# Sending_end.net
KiCad netlist of a schematic drawn in EAGLE
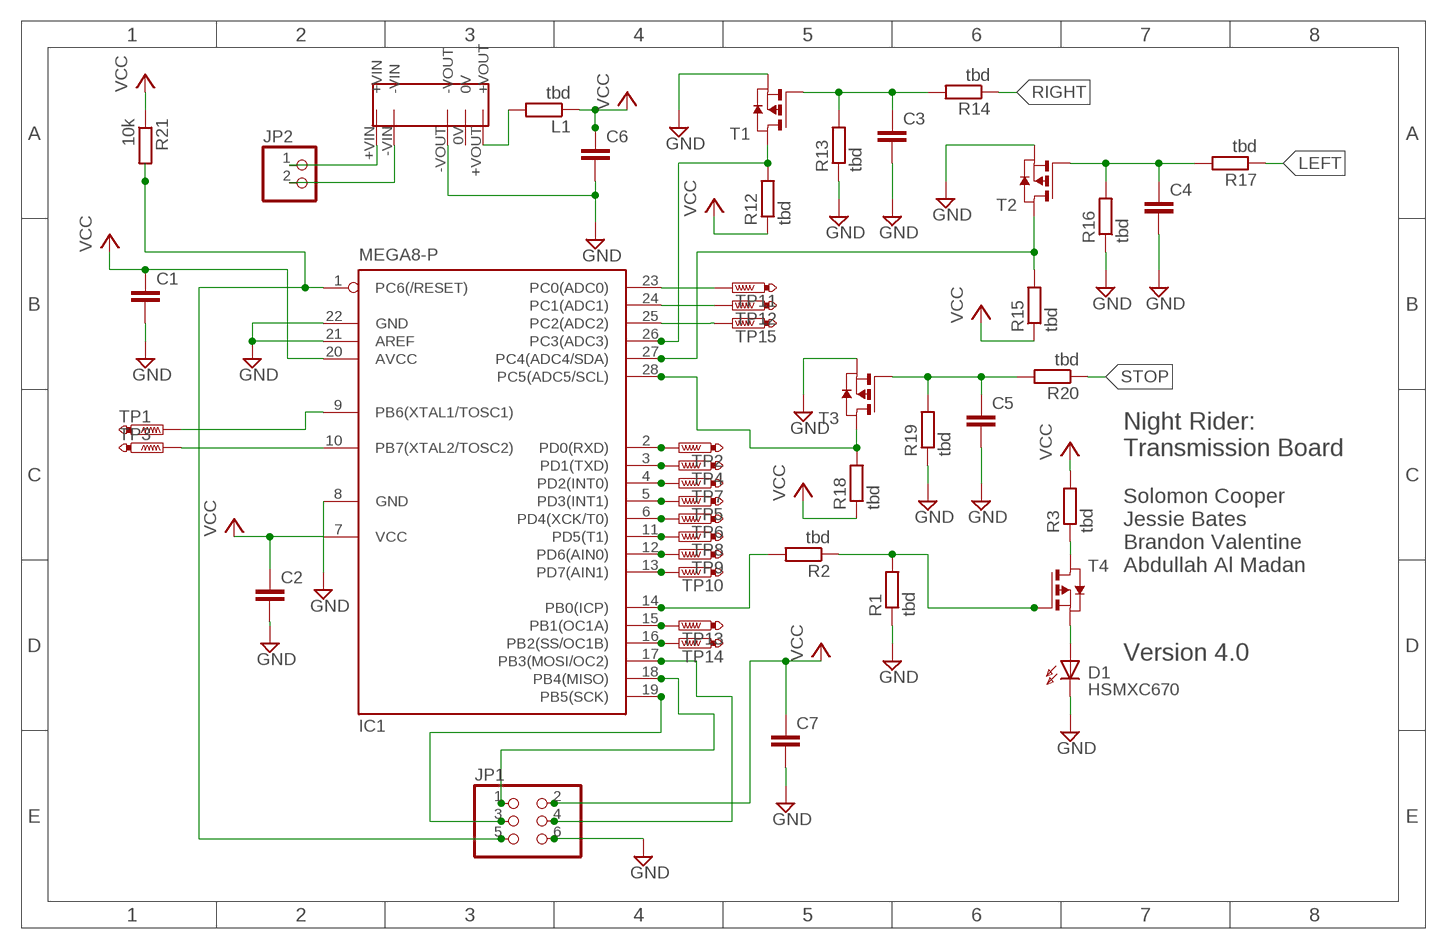
[diagram p0: schematic, sheet 1]

(export (version "E")
  (design (tool "Eeschema 10.0.6"))
  (components
    (comp (ref "C1")
      (value "C-EUC0805")
      (footprint "eagle-import:C0805")
      (libsource (lib "eagle-import") (part "C-EUC0805"))
    )
    (comp (ref "C2")
      (value "C-EUC0805")
      (footprint "eagle-import:C0805")
      (libsource (lib "eagle-import") (part "C-EUC0805"))
    )
    (comp (ref "C3")
      (value "C-EUC0805")
      (footprint "eagle-import:C0805")
      (libsource (lib "eagle-import") (part "C-EUC0805"))
    )
    (comp (ref "C4")
      (value "C-EUC0805")
      (footprint "eagle-import:C0805")
      (libsource (lib "eagle-import") (part "C-EUC0805"))
    )
    (comp (ref "C5")
      (value "C-EUC0805")
      (footprint "eagle-import:C0805")
      (libsource (lib "eagle-import") (part "C-EUC0805"))
    )
    (comp (ref "C6")
      (value "C-EUC0805")
      (footprint "eagle-import:C0805")
      (libsource (lib "eagle-import") (part "C-EUC0805"))
    )
    (comp (ref "C7")
      (value "C-EUC0805")
      (footprint "eagle-import:C0805")
      (libsource (lib "eagle-import") (part "C-EUC0805"))
    )
    (comp (ref "D1")
      (value "HSMXC670")
      (footprint "eagle-import:HSMXC670")
      (fields (field (name "OC_FARNELL") "unknown") (field (name "OC_NEWARK") "unknown"))
      (libsource (lib "eagle-import") (part "HSMXC670"))
    )
    (comp (ref "IC1")
      (value "MEGA8-P")
      (footprint "eagle-import:DIL28-3")
      (libsource (lib "eagle-import") (part "MEGA8-P"))
    )
    (comp (ref "JP1")
      (value "PINHD-2X3")
      (footprint "eagle-import:2X03")
      (libsource (lib "eagle-import") (part "PINHD-2X3"))
    )
    (comp (ref "JP2")
      (value "PINHD-1X2")
      (footprint "eagle-import:1X02")
      (libsource (lib "eagle-import") (part "PINHD-1X2"))
    )
    (comp (ref "L1")
      (value "tbd")
      (footprint "eagle-import:M0805")
      (libsource (lib "eagle-import") (part "R-EU_M0805"))
    )
    (comp (ref "R1")
      (value "tbd")
      (footprint "eagle-import:M0805")
      (libsource (lib "eagle-import") (part "R-EU_M0805"))
    )
    (comp (ref "R2")
      (value "tbd")
      (footprint "eagle-import:M0805")
      (libsource (lib "eagle-import") (part "R-EU_M0805"))
    )
    (comp (ref "R3")
      (value "tbd")
      (footprint "eagle-import:M0805")
      (libsource (lib "eagle-import") (part "R-EU_M0805"))
    )
    (comp (ref "R12")
      (value "tbd")
      (footprint "eagle-import:M0805")
      (libsource (lib "eagle-import") (part "R-EU_M0805"))
    )
    (comp (ref "R13")
      (value "tbd")
      (footprint "eagle-import:M0805")
      (libsource (lib "eagle-import") (part "R-EU_M0805"))
    )
    (comp (ref "R14")
      (value "tbd")
      (footprint "eagle-import:M0805")
      (libsource (lib "eagle-import") (part "R-EU_M0805"))
    )
    (comp (ref "R15")
      (value "tbd")
      (footprint "eagle-import:M0805")
      (libsource (lib "eagle-import") (part "R-EU_M0805"))
    )
    (comp (ref "R16")
      (value "tbd")
      (footprint "eagle-import:M0805")
      (libsource (lib "eagle-import") (part "R-EU_M0805"))
    )
    (comp (ref "R17")
      (value "tbd")
      (footprint "eagle-import:M0805")
      (libsource (lib "eagle-import") (part "R-EU_M0805"))
    )
    (comp (ref "R18")
      (value "tbd")
      (footprint "eagle-import:M0805")
      (libsource (lib "eagle-import") (part "R-EU_M0805"))
    )
    (comp (ref "R19")
      (value "tbd")
      (footprint "eagle-import:M0805")
      (libsource (lib "eagle-import") (part "R-EU_M0805"))
    )
    (comp (ref "R20")
      (value "tbd")
      (footprint "eagle-import:M0805")
      (libsource (lib "eagle-import") (part "R-EU_M0805"))
    )
    (comp (ref "R21")
      (value "10k")
      (footprint "eagle-import:M0805")
      (libsource (lib "eagle-import") (part "R-EU_M0805"))
    )
    (comp (ref "T1")
      (value "PMOSSOT23")
      (footprint "eagle-import:SOT-23")
      (libsource (lib "eagle-import") (part "PMOSSOT23"))
    )
    (comp (ref "T2")
      (value "PMOSSOT23")
      (footprint "eagle-import:SOT-23")
      (libsource (lib "eagle-import") (part "PMOSSOT23"))
    )
    (comp (ref "T3")
      (value "PMOSSOT23")
      (footprint "eagle-import:SOT-23")
      (libsource (lib "eagle-import") (part "PMOSSOT23"))
    )
    (comp (ref "T4")
      (value "PMOSSOT23")
      (footprint "eagle-import:SOT-23")
      (fields (field (name "OC_FARNELL") "unknown") (field (name "OC_NEWARK") "unknown"))
      (libsource (lib "eagle-import") (part "PMOSSOT23"))
    )
    (comp (ref "TP1")
      (value "PTR1PAD1-20")
      (footprint "eagle-import:P1-20")
      (libsource (lib "eagle-import") (part "PTR1PAD1-20"))
    )
    (comp (ref "TP2")
      (value "PTR1PAD1-20")
      (footprint "eagle-import:P1-20")
      (libsource (lib "eagle-import") (part "PTR1PAD1-20"))
    )
    (comp (ref "TP3")
      (value "PTR1PAD1-20")
      (footprint "eagle-import:P1-20")
      (libsource (lib "eagle-import") (part "PTR1PAD1-20"))
    )
    (comp (ref "TP4")
      (value "PTR1PAD1-20")
      (footprint "eagle-import:P1-20")
      (libsource (lib "eagle-import") (part "PTR1PAD1-20"))
    )
    (comp (ref "TP5")
      (value "PTR1PAD1-20")
      (footprint "eagle-import:P1-20")
      (libsource (lib "eagle-import") (part "PTR1PAD1-20"))
    )
    (comp (ref "TP6")
      (value "PTR1PAD1-20")
      (footprint "eagle-import:P1-20")
      (libsource (lib "eagle-import") (part "PTR1PAD1-20"))
    )
    (comp (ref "TP7")
      (value "PTR1PAD1-20")
      (footprint "eagle-import:P1-20")
      (libsource (lib "eagle-import") (part "PTR1PAD1-20"))
    )
    (comp (ref "TP8")
      (value "PTR1PAD1-20")
      (footprint "eagle-import:P1-20")
      (libsource (lib "eagle-import") (part "PTR1PAD1-20"))
    )
    (comp (ref "TP9")
      (value "PTR1PAD1-20")
      (footprint "eagle-import:P1-20")
      (libsource (lib "eagle-import") (part "PTR1PAD1-20"))
    )
    (comp (ref "TP10")
      (value "PTR1PAD1-20")
      (footprint "eagle-import:P1-20")
      (libsource (lib "eagle-import") (part "PTR1PAD1-20"))
    )
    (comp (ref "TP11")
      (value "PTR1PAD1-20")
      (footprint "eagle-import:P1-20")
      (libsource (lib "eagle-import") (part "PTR1PAD1-20"))
    )
    (comp (ref "TP12")
      (value "PTR1PAD1-20")
      (footprint "eagle-import:P1-20")
      (libsource (lib "eagle-import") (part "PTR1PAD1-20"))
    )
    (comp (ref "TP13")
      (value "PTR1PAD1-20")
      (footprint "eagle-import:P1-20")
      (libsource (lib "eagle-import") (part "PTR1PAD1-20"))
    )
    (comp (ref "TP14")
      (value "PTR1PAD1-20")
      (footprint "eagle-import:P1-20")
      (libsource (lib "eagle-import") (part "PTR1PAD1-20"))
    )
    (comp (ref "TP15")
      (value "PTR1PAD1-20")
      (footprint "eagle-import:P1-20")
      (libsource (lib "eagle-import") (part "PTR1PAD1-20"))
    )
    (comp (ref "U$1")
      (value "NKA1205SC")
      (footprint "eagle-import:NKA1205SC")
      (libsource (lib "eagle-import") (part "NKA1205SC"))
    )
  )
  (nets
    (net (code "1") (name "GND") (class "Default")
      (node (ref "C1") (pin "2") (pinfunction "2_2") (pintype "passive"))
      (node (ref "C2") (pin "2") (pinfunction "2_2") (pintype "passive"))
      (node (ref "C3") (pin "2") (pinfunction "2_2") (pintype "passive"))
      (node (ref "C4") (pin "2") (pinfunction "2_2") (pintype "passive"))
      (node (ref "C5") (pin "2") (pinfunction "2_2") (pintype "passive"))
      (node (ref "C6") (pin "2") (pinfunction "2_2") (pintype "passive"))
      (node (ref "C7") (pin "2") (pinfunction "2_2") (pintype "passive"))
      (node (ref "D1") (pin "K") (pinfunction "C_K") (pintype "passive"))
      (node (ref "IC1") (pin "21") (pinfunction "AREF_21") (pintype "passive"))
      (node (ref "IC1") (pin "22") (pinfunction "GND_22") (pintype "power_in"))
      (node (ref "IC1") (pin "8") (pinfunction "GND_8") (pintype "power_in"))
      (node (ref "JP1") (pin "6") (pinfunction "6_6") (pintype "passive"))
      (node (ref "R1") (pin "1") (pinfunction "1_1") (pintype "passive"))
      (node (ref "R13") (pin "1") (pinfunction "1_1") (pintype "passive"))
      (node (ref "R16") (pin "1") (pinfunction "1_1") (pintype "passive"))
      (node (ref "R19") (pin "1") (pinfunction "1_1") (pintype "passive"))
      (node (ref "T1") (pin "2") (pinfunction "S_2") (pintype "passive"))
      (node (ref "T2") (pin "2") (pinfunction "S_2") (pintype "passive"))
      (node (ref "T3") (pin "2") (pinfunction "S_2") (pintype "passive"))
      (node (ref "U$1") (pin "-VOUT") (pinfunction "-VOUT_-VOUT") (pintype "bidirectional"))
    )
    (net (code "2") (name "LEFT") (class "Default")
      (node (ref "R17") (pin "1") (pinfunction "1_1") (pintype "passive"))
    )
    (net (code "3") (name "Net-(IC1-PB0(ICP))") (class "Default")
      (node (ref "IC1") (pin "14") (pinfunction "PB0(ICP)_14") (pintype "bidirectional"))
      (node (ref "R2") (pin "2") (pinfunction "2_2") (pintype "passive"))
    )
    (net (code "4") (name "Net-(IC1-PB1(OC1A))") (class "Default")
      (node (ref "IC1") (pin "15") (pinfunction "PB1(OC1A)_15") (pintype "bidirectional"))
      (node (ref "TP13") (pin "TP") (pinfunction "TP_TP") (pintype "input"))
    )
    (net (code "5") (name "Net-(IC1-PB2(SS{slash}OC1B))") (class "Default")
      (node (ref "IC1") (pin "16") (pinfunction "PB2(SS/OC1B)_16") (pintype "bidirectional"))
      (node (ref "TP14") (pin "TP") (pinfunction "TP_TP") (pintype "input"))
    )
    (net (code "6") (name "Net-(IC1-PB3(MOSI{slash}OC2))") (class "Default")
      (node (ref "IC1") (pin "17") (pinfunction "PB3(MOSI/OC2)_17") (pintype "bidirectional"))
      (node (ref "JP1") (pin "4") (pinfunction "4_4") (pintype "passive"))
    )
    (net (code "7") (name "Net-(IC1-PB4(MISO))") (class "Default")
      (node (ref "IC1") (pin "18") (pinfunction "PB4(MISO)_18") (pintype "bidirectional"))
      (node (ref "JP1") (pin "1") (pinfunction "1_1") (pintype "passive"))
    )
    (net (code "8") (name "Net-(IC1-PB5(SCK))") (class "Default")
      (node (ref "IC1") (pin "19") (pinfunction "PB5(SCK)_19") (pintype "bidirectional"))
      (node (ref "JP1") (pin "3") (pinfunction "3_3") (pintype "passive"))
    )
    (net (code "9") (name "Net-(IC1-PB6(XTAL1{slash}TOSC1))") (class "Default")
      (node (ref "IC1") (pin "9") (pinfunction "PB6(XTAL1/TOSC1)_9") (pintype "bidirectional"))
      (node (ref "TP1") (pin "TP") (pinfunction "TP_TP") (pintype "input"))
    )
    (net (code "10") (name "Net-(IC1-PB7(XTAL2{slash}TOSC2))") (class "Default")
      (node (ref "IC1") (pin "10") (pinfunction "PB7(XTAL2/TOSC2)_10") (pintype "bidirectional"))
      (node (ref "TP3") (pin "TP") (pinfunction "TP_TP") (pintype "input"))
    )
    (net (code "11") (name "Net-(IC1-PC0(ADC0))") (class "Default")
      (node (ref "IC1") (pin "23") (pinfunction "PC0(ADC0)_23") (pintype "bidirectional"))
      (node (ref "TP11") (pin "TP") (pinfunction "TP_TP") (pintype "input"))
    )
    (net (code "12") (name "Net-(IC1-PC1(ADC1))") (class "Default")
      (node (ref "IC1") (pin "24") (pinfunction "PC1(ADC1)_24") (pintype "bidirectional"))
      (node (ref "TP12") (pin "TP") (pinfunction "TP_TP") (pintype "input"))
    )
    (net (code "13") (name "Net-(IC1-PC2(ADC2))") (class "Default")
      (node (ref "IC1") (pin "25") (pinfunction "PC2(ADC2)_25") (pintype "bidirectional"))
      (node (ref "TP15") (pin "TP") (pinfunction "TP_TP") (pintype "input"))
    )
    (net (code "14") (name "Net-(IC1-PC3(ADC3))") (class "Default")
      (node (ref "IC1") (pin "26") (pinfunction "PC3(ADC3)_26") (pintype "bidirectional"))
      (node (ref "R12") (pin "2") (pinfunction "2_2") (pintype "passive"))
      (node (ref "T1") (pin "1") (pinfunction "D_1") (pintype "passive"))
    )
    (net (code "15") (name "Net-(IC1-PC4(ADC4{slash}SDA))") (class "Default")
      (node (ref "IC1") (pin "27") (pinfunction "PC4(ADC4/SDA)_27") (pintype "bidirectional"))
      (node (ref "R15") (pin "2") (pinfunction "2_2") (pintype "passive"))
      (node (ref "T2") (pin "1") (pinfunction "D_1") (pintype "passive"))
    )
    (net (code "16") (name "Net-(IC1-PC5(ADC5{slash}SCL))") (class "Default")
      (node (ref "IC1") (pin "28") (pinfunction "PC5(ADC5/SCL)_28") (pintype "bidirectional"))
      (node (ref "R18") (pin "2") (pinfunction "2_2") (pintype "passive"))
      (node (ref "T3") (pin "1") (pinfunction "D_1") (pintype "passive"))
    )
    (net (code "17") (name "Net-(IC1-PC6({slash}RESET))") (class "Default")
      (node (ref "IC1") (pin "1") (pinfunction "PC6(/RESET)_1") (pintype "bidirectional"))
      (node (ref "JP1") (pin "5") (pinfunction "5_5") (pintype "passive"))
      (node (ref "R21") (pin "2") (pinfunction "2_2") (pintype "passive"))
    )
    (net (code "18") (name "Net-(IC1-PD0(RXD))") (class "Default")
      (node (ref "IC1") (pin "2") (pinfunction "PD0(RXD)_2") (pintype "bidirectional"))
      (node (ref "TP2") (pin "TP") (pinfunction "TP_TP") (pintype "input"))
    )
    (net (code "19") (name "Net-(IC1-PD1(TXD))") (class "Default")
      (node (ref "IC1") (pin "3") (pinfunction "PD1(TXD)_3") (pintype "bidirectional"))
      (node (ref "TP4") (pin "TP") (pinfunction "TP_TP") (pintype "input"))
    )
    (net (code "20") (name "Net-(IC1-PD2(INT0))") (class "Default")
      (node (ref "IC1") (pin "4") (pinfunction "PD2(INT0)_4") (pintype "bidirectional"))
      (node (ref "TP7") (pin "TP") (pinfunction "TP_TP") (pintype "input"))
    )
    (net (code "21") (name "Net-(IC1-PD3(INT1))") (class "Default")
      (node (ref "IC1") (pin "5") (pinfunction "PD3(INT1)_5") (pintype "bidirectional"))
      (node (ref "TP5") (pin "TP") (pinfunction "TP_TP") (pintype "input"))
    )
    (net (code "22") (name "Net-(IC1-PD4(XCK{slash}T0))") (class "Default")
      (node (ref "IC1") (pin "6") (pinfunction "PD4(XCK/T0)_6") (pintype "bidirectional"))
      (node (ref "TP6") (pin "TP") (pinfunction "TP_TP") (pintype "input"))
    )
    (net (code "23") (name "Net-(IC1-PD5(T1))") (class "Default")
      (node (ref "IC1") (pin "11") (pinfunction "PD5(T1)_11") (pintype "bidirectional"))
      (node (ref "TP8") (pin "TP") (pinfunction "TP_TP") (pintype "input"))
    )
    (net (code "24") (name "Net-(IC1-PD6(AIN0))") (class "Default")
      (node (ref "IC1") (pin "12") (pinfunction "PD6(AIN0)_12") (pintype "bidirectional"))
      (node (ref "TP9") (pin "TP") (pinfunction "TP_TP") (pintype "input"))
    )
    (net (code "25") (name "Net-(IC1-PD7(AIN1))") (class "Default")
      (node (ref "IC1") (pin "13") (pinfunction "PD7(AIN1)_13") (pintype "bidirectional"))
      (node (ref "TP10") (pin "TP") (pinfunction "TP_TP") (pintype "input"))
    )
    (net (code "26") (name "Net-(JP2-Pad1)") (class "Default")
      (node (ref "JP2") (pin "1") (pinfunction "1_1") (pintype "passive"))
      (node (ref "U$1") (pin "+VIN") (pinfunction "+VIN_+VIN") (pintype "bidirectional"))
    )
    (net (code "27") (name "Net-(JP2-Pad2)") (class "Default")
      (node (ref "JP2") (pin "2") (pinfunction "2_2") (pintype "passive"))
      (node (ref "U$1") (pin "-VIN") (pinfunction "-VIN_-VIN") (pintype "bidirectional"))
    )
    (net (code "28") (name "Net-(L1-Pad2)") (class "Default")
      (node (ref "L1") (pin "2") (pinfunction "2_2") (pintype "passive"))
      (node (ref "U$1") (pin "+VOUT") (pinfunction "+VOUT_+VOUT") (pintype "bidirectional"))
    )
    (net (code "29") (name "Net-(T1-G)") (class "Default")
      (node (ref "C3") (pin "1") (pinfunction "1_1") (pintype "passive"))
      (node (ref "R13") (pin "2") (pinfunction "2_2") (pintype "passive"))
      (node (ref "R14") (pin "2") (pinfunction "2_2") (pintype "passive"))
      (node (ref "T1") (pin "3") (pinfunction "G_3") (pintype "passive"))
    )
    (net (code "30") (name "Net-(T2-G)") (class "Default")
      (node (ref "C4") (pin "1") (pinfunction "1_1") (pintype "passive"))
      (node (ref "R16") (pin "2") (pinfunction "2_2") (pintype "passive"))
      (node (ref "R17") (pin "2") (pinfunction "2_2") (pintype "passive"))
      (node (ref "T2") (pin "3") (pinfunction "G_3") (pintype "passive"))
    )
    (net (code "31") (name "Net-(T3-G)") (class "Default")
      (node (ref "C5") (pin "1") (pinfunction "1_1") (pintype "passive"))
      (node (ref "R19") (pin "2") (pinfunction "2_2") (pintype "passive"))
      (node (ref "R20") (pin "2") (pinfunction "2_2") (pintype "passive"))
      (node (ref "T3") (pin "3") (pinfunction "G_3") (pintype "passive"))
    )
    (net (code "32") (name "Net-(T4-D)") (class "Default")
      (node (ref "R3") (pin "1") (pinfunction "1_1") (pintype "passive"))
      (node (ref "T4") (pin "1") (pinfunction "D_1") (pintype "passive"))
    )
    (net (code "33") (name "Net-(T4-G)") (class "Default")
      (node (ref "R1") (pin "2") (pinfunction "2_2") (pintype "passive"))
      (node (ref "R2") (pin "1") (pinfunction "1_1") (pintype "passive"))
      (node (ref "T4") (pin "3") (pinfunction "G_3") (pintype "passive"))
    )
    (net (code "34") (name "Net-(T4-S)") (class "Default")
      (node (ref "D1") (pin "A") (pinfunction "A_A") (pintype "passive"))
      (node (ref "T4") (pin "2") (pinfunction "S_2") (pintype "passive"))
    )
    (net (code "35") (name "RIGHT") (class "Default")
      (node (ref "R14") (pin "1") (pinfunction "1_1") (pintype "passive"))
    )
    (net (code "36") (name "STOP") (class "Default")
      (node (ref "R20") (pin "1") (pinfunction "1_1") (pintype "passive"))
    )
    (net (code "37") (name "VCC") (class "Default")
      (node (ref "C1") (pin "1") (pinfunction "1_1") (pintype "passive"))
      (node (ref "C2") (pin "1") (pinfunction "1_1") (pintype "passive"))
      (node (ref "C6") (pin "1") (pinfunction "1_1") (pintype "passive"))
      (node (ref "C7") (pin "1") (pinfunction "1_1") (pintype "passive"))
      (node (ref "IC1") (pin "20") (pinfunction "AVCC_20") (pintype "power_in"))
      (node (ref "IC1") (pin "7") (pinfunction "VCC_7") (pintype "power_in"))
      (node (ref "JP1") (pin "2") (pinfunction "2_2") (pintype "passive"))
      (node (ref "L1") (pin "1") (pinfunction "1_1") (pintype "passive"))
      (node (ref "R12") (pin "1") (pinfunction "1_1") (pintype "passive"))
      (node (ref "R15") (pin "1") (pinfunction "1_1") (pintype "passive"))
      (node (ref "R18") (pin "1") (pinfunction "1_1") (pintype "passive"))
      (node (ref "R21") (pin "1") (pinfunction "1_1") (pintype "passive"))
      (node (ref "R3") (pin "2") (pinfunction "2_2") (pintype "passive"))
    )
    (net (code "38") (name "unconnected-(U$1-Pad0V)") (class "Default")
      (node (ref "U$1") (pin "0V") (pinfunction "0V_0V") (pintype "bidirectional"))
    )
  )
)
